# 3x3_v2.net
KiCad netlist of a schematic drawn in Altium Designer
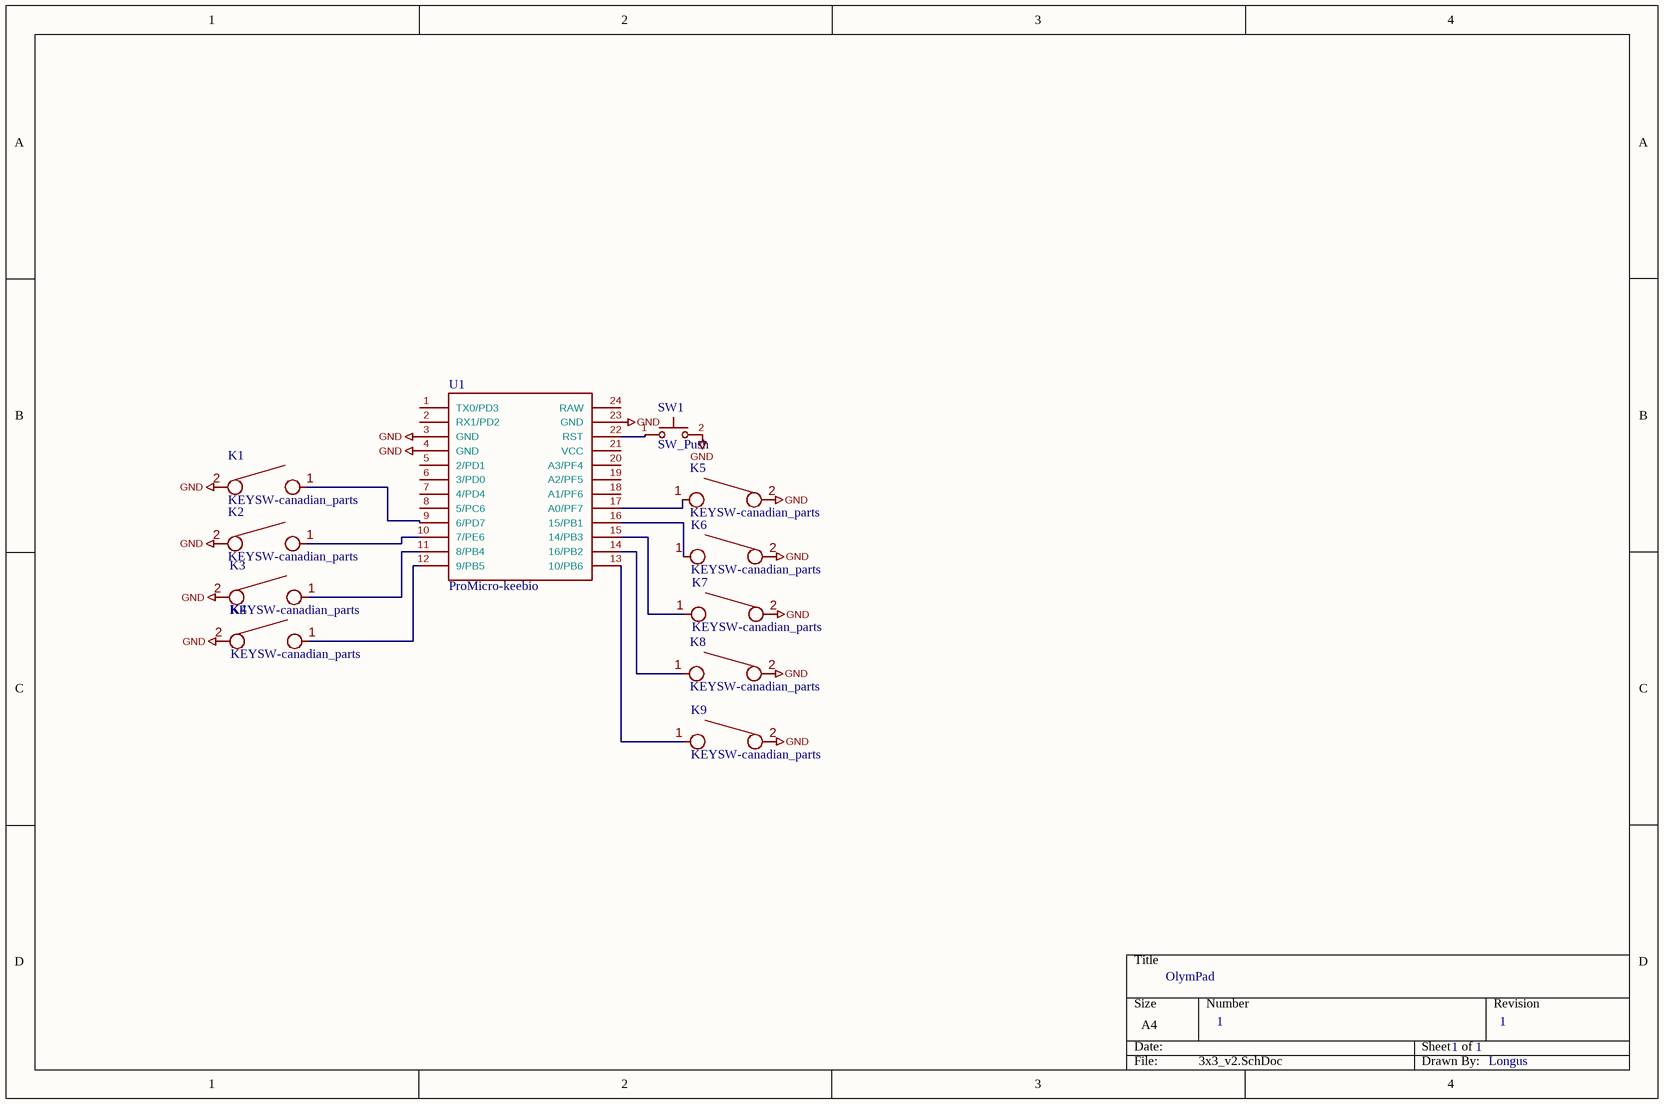
[diagram p0: 3x3_v2.SchDoc]

(export (version "E")
  (design (tool "Eeschema 10.0.6"))
  (components
    (comp (ref "K1")
      (value "KEYSW-canadian_parts")
      (footprint "Socket")
      (libsource (lib "Macropad") (part "KEYSW-canadian_parts"))
    )
    (comp (ref "K2")
      (value "KEYSW-canadian_parts")
      (footprint "Socket")
      (libsource (lib "Macropad") (part "KEYSW-canadian_parts"))
    )
    (comp (ref "K3")
      (value "KEYSW-canadian_parts")
      (footprint "Socket")
      (libsource (lib "Macropad") (part "KEYSW-canadian_parts"))
    )
    (comp (ref "K4")
      (value "KEYSW-canadian_parts")
      (footprint "Socket")
      (libsource (lib "Macropad") (part "KEYSW-canadian_parts"))
    )
    (comp (ref "K5")
      (value "KEYSW-canadian_parts")
      (footprint "Socket")
      (libsource (lib "Macropad") (part "KEYSW-canadian_parts"))
    )
    (comp (ref "K6")
      (value "KEYSW-canadian_parts")
      (footprint "Socket")
      (libsource (lib "Macropad") (part "KEYSW-canadian_parts"))
    )
    (comp (ref "K7")
      (value "KEYSW-canadian_parts")
      (footprint "Socket")
      (libsource (lib "Macropad") (part "KEYSW-canadian_parts"))
    )
    (comp (ref "K8")
      (value "KEYSW-canadian_parts")
      (footprint "Socket")
      (libsource (lib "Macropad") (part "KEYSW-canadian_parts"))
    )
    (comp (ref "K9")
      (value "KEYSW-canadian_parts")
      (footprint "Socket")
      (libsource (lib "Macropad") (part "KEYSW-canadian_parts"))
    )
    (comp (ref "SW1") (value "SW_Push") (footprint "Reset") (libsource (lib "Macropad") (part "SW_Push")))
    (comp (ref "U1")
      (value "ProMicro-keebio")
      (footprint "Pro-Micro")
      (libsource (lib "Macropad") (part "ProMicro-keebio"))
    )
  )
  (nets
    (net (code "1") (name "GND") (class "Default")
      (node (ref "K1") (pin "2") (pinfunction "2_2") (pintype "passive"))
      (node (ref "K2") (pin "2") (pinfunction "2_2") (pintype "passive"))
      (node (ref "K3") (pin "2") (pinfunction "2_2") (pintype "passive"))
      (node (ref "K4") (pin "2") (pinfunction "2_2") (pintype "passive"))
      (node (ref "K5") (pin "2") (pinfunction "2_2") (pintype "passive"))
      (node (ref "K6") (pin "2") (pinfunction "2_2") (pintype "passive"))
      (node (ref "K7") (pin "2") (pinfunction "2_2") (pintype "passive"))
      (node (ref "K8") (pin "2") (pinfunction "2_2") (pintype "passive"))
      (node (ref "K9") (pin "2") (pinfunction "2_2") (pintype "passive"))
      (node (ref "SW1") (pin "2") (pinfunction "2_2") (pintype "passive"))
      (node (ref "U1") (pin "23") (pinfunction "GND_23") (pintype "passive"))
      (node (ref "U1") (pin "3") (pinfunction "GND_3") (pintype "passive"))
      (node (ref "U1") (pin "4") (pinfunction "GND_4") (pintype "passive"))
    )
    (net (code "2") (name "Net-(U1-6{slash}PD7)") (class "Default")
      (node (ref "K1") (pin "1") (pinfunction "1_1") (pintype "passive"))
      (node (ref "U1") (pin "9") (pinfunction "6/PD7_9") (pintype "passive"))
    )
    (net (code "3") (name "Net-(U1-7{slash}PE6)") (class "Default")
      (node (ref "K2") (pin "1") (pinfunction "1_1") (pintype "passive"))
      (node (ref "U1") (pin "10") (pinfunction "7/PE6_10") (pintype "passive"))
    )
    (net (code "4") (name "Net-(U1-8{slash}PB4)") (class "Default")
      (node (ref "K3") (pin "1") (pinfunction "1_1") (pintype "passive"))
      (node (ref "U1") (pin "11") (pinfunction "8/PB4_11") (pintype "passive"))
    )
    (net (code "5") (name "Net-(U1-9{slash}PB5)") (class "Default")
      (node (ref "K4") (pin "1") (pinfunction "1_1") (pintype "passive"))
      (node (ref "U1") (pin "12") (pinfunction "9/PB5_12") (pintype "passive"))
    )
    (net (code "6") (name "Net-(U1-10{slash}PB6)") (class "Default")
      (node (ref "K9") (pin "1") (pinfunction "1_1") (pintype "passive"))
      (node (ref "U1") (pin "13") (pinfunction "10/PB6_13") (pintype "passive"))
    )
    (net (code "7") (name "Net-(U1-14{slash}PB3)") (class "Default")
      (node (ref "K7") (pin "1") (pinfunction "1_1") (pintype "passive"))
      (node (ref "U1") (pin "15") (pinfunction "14/PB3_15") (pintype "passive"))
    )
    (net (code "8") (name "Net-(U1-15{slash}PB1)") (class "Default")
      (node (ref "K6") (pin "1") (pinfunction "1_1") (pintype "passive"))
      (node (ref "U1") (pin "16") (pinfunction "15/PB1_16") (pintype "passive"))
    )
    (net (code "9") (name "Net-(U1-16{slash}PB2)") (class "Default")
      (node (ref "K8") (pin "1") (pinfunction "1_1") (pintype "passive"))
      (node (ref "U1") (pin "14") (pinfunction "16/PB2_14") (pintype "passive"))
    )
    (net (code "10") (name "Net-(U1-A0{slash}PF7)") (class "Default")
      (node (ref "K5") (pin "1") (pinfunction "1_1") (pintype "passive"))
      (node (ref "U1") (pin "17") (pinfunction "A0/PF7_17") (pintype "passive"))
    )
    (net (code "11") (name "Net-(U1-RST)") (class "Default")
      (node (ref "SW1") (pin "1") (pinfunction "1_1") (pintype "passive"))
      (node (ref "U1") (pin "22") (pinfunction "RST_22") (pintype "passive"))
    )
    (net (code "12") (name "unconnected-(U1-2{slash}PD1-Pad5)") (class "Default")
      (node (ref "U1") (pin "5") (pinfunction "2/PD1_5") (pintype "passive"))
    )
    (net (code "13") (name "unconnected-(U1-3{slash}PD0-Pad6)") (class "Default")
      (node (ref "U1") (pin "6") (pinfunction "3/PD0_6") (pintype "passive"))
    )
    (net (code "14") (name "unconnected-(U1-4{slash}PD4-Pad7)") (class "Default")
      (node (ref "U1") (pin "7") (pinfunction "4/PD4_7") (pintype "passive"))
    )
    (net (code "15") (name "unconnected-(U1-5{slash}PC6-Pad8)") (class "Default")
      (node (ref "U1") (pin "8") (pinfunction "5/PC6_8") (pintype "passive"))
    )
    (net (code "16") (name "unconnected-(U1-A1{slash}PF6-Pad18)") (class "Default")
      (node (ref "U1") (pin "18") (pinfunction "A1/PF6_18") (pintype "passive"))
    )
    (net (code "17") (name "unconnected-(U1-A2{slash}PF5-Pad19)") (class "Default")
      (node (ref "U1") (pin "19") (pinfunction "A2/PF5_19") (pintype "passive"))
    )
    (net (code "18") (name "unconnected-(U1-A3{slash}PF4-Pad20)") (class "Default")
      (node (ref "U1") (pin "20") (pinfunction "A3/PF4_20") (pintype "passive"))
    )
    (net (code "19") (name "unconnected-(U1-RAW-Pad24)") (class "Default")
      (node (ref "U1") (pin "24") (pinfunction "RAW_24") (pintype "passive"))
    )
    (net (code "20") (name "unconnected-(U1-RX1{slash}PD2-Pad2)") (class "Default")
      (node (ref "U1") (pin "2") (pinfunction "RX1/PD2_2") (pintype "passive"))
    )
    (net (code "21") (name "unconnected-(U1-TX0{slash}PD3-Pad1)") (class "Default")
      (node (ref "U1") (pin "1") (pinfunction "TX0/PD3_1") (pintype "passive"))
    )
    (net (code "22") (name "unconnected-(U1-VCC-Pad21)") (class "Default")
      (node (ref "U1") (pin "21") (pinfunction "VCC_21") (pintype "passive"))
    )
  )
)
